# vocal_6btns.net
KiCad netlist of a schematic drawn in EAGLE
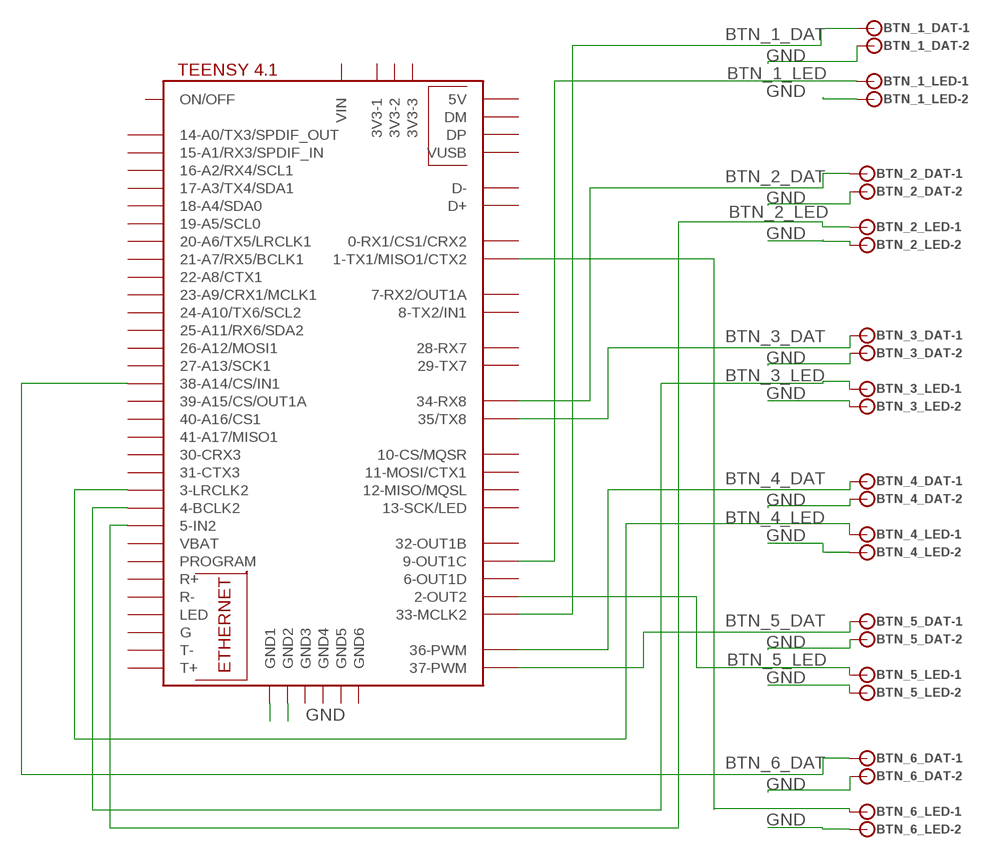
[diagram p0: schematic, sheet 1]

(export (version "E")
  (design (tool "Eeschema 10.0.6"))
  (components
    (comp (ref "BTN_1_DAT")
      (value "JST-XH-2B")
      (footprint "eagle-import:B2B-XH-A")
      (fields (field (name "MF") "JST") (field (name "MPN") "B2B-XH-A"))
      (libsource (lib "eagle-import") (part "JST-XH-2B"))
    )
    (comp (ref "BTN_1_LED")
      (value "JST-XH-2B")
      (footprint "eagle-import:B2B-XH-A")
      (fields (field (name "MF") "JST") (field (name "MPN") "B2B-XH-A"))
      (libsource (lib "eagle-import") (part "JST-XH-2B"))
    )
    (comp (ref "BTN_2_DAT")
      (value "JST-XH-2B")
      (footprint "eagle-import:B2B-XH-A")
      (fields (field (name "MF") "JST") (field (name "MPN") "B2B-XH-A"))
      (libsource (lib "eagle-import") (part "JST-XH-2B"))
    )
    (comp (ref "BTN_2_LED")
      (value "JST-XH-2B")
      (footprint "eagle-import:B2B-XH-A")
      (fields (field (name "MF") "JST") (field (name "MPN") "B2B-XH-A"))
      (libsource (lib "eagle-import") (part "JST-XH-2B"))
    )
    (comp (ref "BTN_3_DAT")
      (value "JST-XH-2B")
      (footprint "eagle-import:B2B-XH-A")
      (fields (field (name "MF") "JST") (field (name "MPN") "B2B-XH-A"))
      (libsource (lib "eagle-import") (part "JST-XH-2B"))
    )
    (comp (ref "BTN_3_LED")
      (value "JST-XH-2B")
      (footprint "eagle-import:B2B-XH-A")
      (fields (field (name "MF") "JST") (field (name "MPN") "B2B-XH-A"))
      (libsource (lib "eagle-import") (part "JST-XH-2B"))
    )
    (comp (ref "BTN_4_DAT")
      (value "JST-XH-2B")
      (footprint "eagle-import:B2B-XH-A")
      (fields (field (name "MF") "JST") (field (name "MPN") "B2B-XH-A"))
      (libsource (lib "eagle-import") (part "JST-XH-2B"))
    )
    (comp (ref "BTN_4_LED")
      (value "JST-XH-2B")
      (footprint "eagle-import:B2B-XH-A")
      (fields (field (name "MF") "JST") (field (name "MPN") "B2B-XH-A"))
      (libsource (lib "eagle-import") (part "JST-XH-2B"))
    )
    (comp (ref "BTN_5_DAT")
      (value "JST-XH-2B")
      (footprint "eagle-import:B2B-XH-A")
      (fields (field (name "MF") "JST") (field (name "MPN") "B2B-XH-A"))
      (libsource (lib "eagle-import") (part "JST-XH-2B"))
    )
    (comp (ref "BTN_5_LED")
      (value "JST-XH-2B")
      (footprint "eagle-import:B2B-XH-A")
      (fields (field (name "MF") "JST") (field (name "MPN") "B2B-XH-A"))
      (libsource (lib "eagle-import") (part "JST-XH-2B"))
    )
    (comp (ref "BTN_6_DAT")
      (value "JST-XH-2B")
      (footprint "eagle-import:B2B-XH-A")
      (fields (field (name "MF") "JST") (field (name "MPN") "B2B-XH-A"))
      (libsource (lib "eagle-import") (part "JST-XH-2B"))
    )
    (comp (ref "BTN_6_LED")
      (value "JST-XH-2B")
      (footprint "eagle-import:B2B-XH-A")
      (fields (field (name "MF") "JST") (field (name "MPN") "B2B-XH-A"))
      (libsource (lib "eagle-import") (part "JST-XH-2B"))
    )
    (comp (ref "U$1")
      (value "TEENSY41")
      (footprint "eagle-import:TEENSY41")
      (libsource (lib "eagle-import") (part "TEENSY41"))
    )
  )
  (nets
    (net (code "1") (name "/BTN_1_DAT") (class "Default")
      (node (ref "BTN_1_DAT") (pin "1") (pinfunction "P_1") (pintype "bidirectional"))
      (node (ref "U$1") (pin "33-MCLK2") (pinfunction "33-MCLK2_33-MCLK2") (pintype "bidirectional"))
    )
    (net (code "2") (name "/BTN_1_LED") (class "Default")
      (node (ref "BTN_1_LED") (pin "1") (pinfunction "P_1") (pintype "bidirectional"))
      (node (ref "U$1") (pin "9-OUT1C") (pinfunction "9-OUT1C_9-OUT1C") (pintype "bidirectional"))
    )
    (net (code "3") (name "/BTN_2_DAT") (class "Default")
      (node (ref "BTN_2_DAT") (pin "1") (pinfunction "P_1") (pintype "bidirectional"))
      (node (ref "U$1") (pin "34-RX8") (pinfunction "34-RX8_34-RX8") (pintype "bidirectional"))
    )
    (net (code "4") (name "/BTN_2_LED") (class "Default")
      (node (ref "BTN_2_LED") (pin "1") (pinfunction "P_1") (pintype "bidirectional"))
      (node (ref "U$1") (pin "5-IN2") (pinfunction "5-IN2_5-IN2") (pintype "bidirectional"))
    )
    (net (code "5") (name "/BTN_3_DAT") (class "Default")
      (node (ref "BTN_3_DAT") (pin "1") (pinfunction "P_1") (pintype "bidirectional"))
      (node (ref "U$1") (pin "35-TX8") (pinfunction "35/TX8_35-TX8") (pintype "bidirectional"))
    )
    (net (code "6") (name "/BTN_3_LED") (class "Default")
      (node (ref "BTN_3_LED") (pin "1") (pinfunction "P_1") (pintype "bidirectional"))
      (node (ref "U$1") (pin "4-BCLK2") (pinfunction "4-BCLK2_4-BCLK2") (pintype "bidirectional"))
    )
    (net (code "7") (name "/BTN_4_DAT") (class "Default")
      (node (ref "BTN_4_DAT") (pin "1") (pinfunction "P_1") (pintype "bidirectional"))
      (node (ref "U$1") (pin "36-PWM") (pinfunction "36-PWM_36-PWM") (pintype "bidirectional"))
    )
    (net (code "8") (name "/BTN_4_LED") (class "Default")
      (node (ref "BTN_4_LED") (pin "1") (pinfunction "P_1") (pintype "bidirectional"))
      (node (ref "U$1") (pin "3-LRCLK2") (pinfunction "3-LRCLK2_3-LRCLK2") (pintype "bidirectional"))
    )
    (net (code "9") (name "/BTN_5_DAT") (class "Default")
      (node (ref "BTN_5_DAT") (pin "1") (pinfunction "P_1") (pintype "bidirectional"))
      (node (ref "U$1") (pin "37-PWM") (pinfunction "37-PWM_37-PWM") (pintype "bidirectional"))
    )
    (net (code "10") (name "/BTN_5_LED") (class "Default")
      (node (ref "BTN_5_LED") (pin "1") (pinfunction "P_1") (pintype "bidirectional"))
      (node (ref "U$1") (pin "2-OUT2") (pinfunction "2-OUT2_2-OUT2") (pintype "bidirectional"))
    )
    (net (code "11") (name "/BTN_6_DAT") (class "Default")
      (node (ref "BTN_6_DAT") (pin "1") (pinfunction "P_1") (pintype "bidirectional"))
      (node (ref "U$1") (pin "38-A14/CS/IN1") (pinfunction "38-A14/CS/IN1_38-A14/CS/IN1") (pintype "bidirectional"))
    )
    (net (code "12") (name "/GND") (class "Default")
      (node (ref "BTN_1_DAT") (pin "2") (pinfunction "P_2") (pintype "bidirectional"))
      (node (ref "BTN_1_LED") (pin "2") (pinfunction "P_2") (pintype "bidirectional"))
      (node (ref "BTN_2_DAT") (pin "2") (pinfunction "P_2") (pintype "bidirectional"))
      (node (ref "BTN_2_LED") (pin "2") (pinfunction "P_2") (pintype "bidirectional"))
      (node (ref "BTN_3_DAT") (pin "2") (pinfunction "P_2") (pintype "bidirectional"))
      (node (ref "BTN_3_LED") (pin "2") (pinfunction "P_2") (pintype "bidirectional"))
      (node (ref "BTN_4_DAT") (pin "2") (pinfunction "P_2") (pintype "bidirectional"))
      (node (ref "BTN_4_LED") (pin "2") (pinfunction "P_2") (pintype "bidirectional"))
      (node (ref "BTN_5_DAT") (pin "2") (pinfunction "P_2") (pintype "bidirectional"))
      (node (ref "BTN_5_LED") (pin "2") (pinfunction "P_2") (pintype "bidirectional"))
      (node (ref "BTN_6_DAT") (pin "2") (pinfunction "P_2") (pintype "bidirectional"))
      (node (ref "BTN_6_LED") (pin "2") (pinfunction "P_2") (pintype "bidirectional"))
      (node (ref "U$1") (pin "GND1") (pinfunction "GND1_GND1") (pintype "bidirectional"))
      (node (ref "U$1") (pin "GND2") (pinfunction "GND2_GND2") (pintype "bidirectional"))
    )
    (net (code "13") (name "Net-(BTN_6_LEDA-P)") (class "Default")
      (node (ref "BTN_6_LED") (pin "1") (pinfunction "P_1") (pintype "bidirectional"))
      (node (ref "U$1") (pin "1-TX1/MISO1/CTX2") (pinfunction "1-TX1/MISO1/CTX2_1-TX1/MISO1/CTX2") (pintype "bidirectional"))
    )
    (net (code "14") (name "unconnected-(U$1-5V-Pad+5V)") (class "Default")
      (node (ref "U$1") (pin "+5V") (pinfunction "5V_+5V") (pintype "bidirectional"))
    )
    (net (code "15") (name "unconnected-(U$1-10-CS{slash}MQSR-Pad10-CS\\MQSR)") (class "Default")
      (node (ref "U$1") (pin "10-CS\\MQSR") (pinfunction "10-CS/MQSR_10-CS\\MQSR") (pintype "bidirectional"))
    )
    (net (code "16") (name "unconnected-(U$1-Pad0-RX1{slash}CS1{slash}CRX2)") (class "Default")
      (node (ref "U$1") (pin "0-RX1/CS1/CRX2") (pinfunction "0-RX1/CS1/CRX2_0-RX1/CS1/CRX2") (pintype "bidirectional"))
    )
    (net (code "17") (name "unconnected-(U$1-Pad3V3-1)") (class "Default")
      (node (ref "U$1") (pin "3V3-1") (pinfunction "3V3-1_3V3-1") (pintype "bidirectional"))
    )
    (net (code "18") (name "unconnected-(U$1-Pad3V3-2)") (class "Default")
      (node (ref "U$1") (pin "3V3-2") (pinfunction "3V3-2_3V3-2") (pintype "bidirectional"))
    )
    (net (code "19") (name "unconnected-(U$1-Pad3V3-3)") (class "Default")
      (node (ref "U$1") (pin "3V3-3") (pinfunction "3V3-3_3V3-3") (pintype "bidirectional"))
    )
    (net (code "20") (name "unconnected-(U$1-Pad6-OUT1D)") (class "Default")
      (node (ref "U$1") (pin "6-OUT1D") (pinfunction "6-OUT1D_6-OUT1D") (pintype "bidirectional"))
    )
    (net (code "21") (name "unconnected-(U$1-Pad7-RX2{slash}OUT1A)") (class "Default")
      (node (ref "U$1") (pin "7-RX2/OUT1A") (pinfunction "7-RX2/OUT1A_7-RX2/OUT1A") (pintype "bidirectional"))
    )
    (net (code "22") (name "unconnected-(U$1-Pad8-TX2{slash}IN1)") (class "Default")
      (node (ref "U$1") (pin "8-TX2/IN1") (pinfunction "8-TX2/IN1_8-TX2/IN1") (pintype "bidirectional"))
    )
    (net (code "23") (name "unconnected-(U$1-Pad11-MOSI{slash}CTX1)") (class "Default")
      (node (ref "U$1") (pin "11-MOSI/CTX1") (pinfunction "11-MOSI/CTX1_11-MOSI/CTX1") (pintype "bidirectional"))
    )
    (net (code "24") (name "unconnected-(U$1-Pad12-MISO{slash}MQSL)") (class "Default")
      (node (ref "U$1") (pin "12-MISO/MQSL") (pinfunction "12-MISO/MQSL_12-MISO/MQSL") (pintype "bidirectional"))
    )
    (net (code "25") (name "unconnected-(U$1-Pad13-SCK{slash}LED)") (class "Default")
      (node (ref "U$1") (pin "13-SCK/LED") (pinfunction "13-SCK/LED_13-SCK/LED") (pintype "bidirectional"))
    )
    (net (code "26") (name "unconnected-(U$1-Pad14-A0{slash}TX3{slash}SPDIF_OUT)") (class "Default")
      (node (ref "U$1") (pin "14-A0/TX3/SPDIF_OUT") (pinfunction "14-A0/TX3/SPDIF_OUT_14-A0/TX3/SPDIF_OUT") (pintype "bidirectional"))
    )
    (net (code "27") (name "unconnected-(U$1-Pad15-A1{slash}RX3{slash}SPDIF_IN)") (class "Default")
      (node (ref "U$1") (pin "15-A1/RX3/SPDIF_IN") (pinfunction "15-A1/RX3/SPDIF_IN_15-A1/RX3/SPDIF_IN") (pintype "bidirectional"))
    )
    (net (code "28") (name "unconnected-(U$1-Pad16-A2{slash}RX4{slash}SCL1)") (class "Default")
      (node (ref "U$1") (pin "16-A2/RX4/SCL1") (pinfunction "16-A2/RX4/SCL1_16-A2/RX4/SCL1") (pintype "bidirectional"))
    )
    (net (code "29") (name "unconnected-(U$1-Pad17-A3{slash}TX4{slash}SDA1)") (class "Default")
      (node (ref "U$1") (pin "17-A3/TX4/SDA1") (pinfunction "17-A3/TX4/SDA1_17-A3/TX4/SDA1") (pintype "bidirectional"))
    )
    (net (code "30") (name "unconnected-(U$1-Pad18-A4{slash}SDA0)") (class "Default")
      (node (ref "U$1") (pin "18-A4/SDA0") (pinfunction "18-A4/SDA0_18-A4/SDA0") (pintype "bidirectional"))
    )
    (net (code "31") (name "unconnected-(U$1-Pad19-A5{slash}SCL0)") (class "Default")
      (node (ref "U$1") (pin "19-A5/SCL0") (pinfunction "19-A5/SCL0_19-A5/SCL0") (pintype "bidirectional"))
    )
    (net (code "32") (name "unconnected-(U$1-Pad20-A6{slash}TX5{slash}LRCLK1)") (class "Default")
      (node (ref "U$1") (pin "20-A6/TX5/LRCLK1") (pinfunction "20-A6/TX5/LRCLK1_20-A6/TX5/LRCLK1") (pintype "bidirectional"))
    )
    (net (code "33") (name "unconnected-(U$1-Pad21-A7{slash}RX5{slash}BCLK1)") (class "Default")
      (node (ref "U$1") (pin "21-A7/RX5/BCLK1") (pinfunction "21-A7/RX5/BCLK1_21-A7/RX5/BCLK1") (pintype "bidirectional"))
    )
    (net (code "34") (name "unconnected-(U$1-Pad22-A8{slash}CTX1)") (class "Default")
      (node (ref "U$1") (pin "22-A8/CTX1") (pinfunction "22-A8/CTX1_22-A8/CTX1") (pintype "bidirectional"))
    )
    (net (code "35") (name "unconnected-(U$1-Pad23-A9{slash}CRX1{slash}MCLK1)") (class "Default")
      (node (ref "U$1") (pin "23-A9/CRX1/MCLK1") (pinfunction "23-A9/CRX1/MCLK1_23-A9/CRX1/MCLK1") (pintype "bidirectional"))
    )
    (net (code "36") (name "unconnected-(U$1-Pad24-A10{slash}TX6{slash}SCL2)") (class "Default")
      (node (ref "U$1") (pin "24-A10/TX6/SCL2") (pinfunction "24-A10/TX6/SCL2_24-A10/TX6/SCL2") (pintype "bidirectional"))
    )
    (net (code "37") (name "unconnected-(U$1-Pad25-A11{slash}RX6{slash}SDA2)") (class "Default")
      (node (ref "U$1") (pin "25-A11/RX6/SDA2") (pinfunction "25-A11/RX6/SDA2_25-A11/RX6/SDA2") (pintype "bidirectional"))
    )
    (net (code "38") (name "unconnected-(U$1-Pad26-A12{slash}MOSI1)") (class "Default")
      (node (ref "U$1") (pin "26-A12/MOSI1") (pinfunction "26-A12/MOSI1_26-A12/MOSI1") (pintype "bidirectional"))
    )
    (net (code "39") (name "unconnected-(U$1-Pad27-A13{slash}SCK1)") (class "Default")
      (node (ref "U$1") (pin "27-A13/SCK1") (pinfunction "27-A13/SCK1_27-A13/SCK1") (pintype "bidirectional"))
    )
    (net (code "40") (name "unconnected-(U$1-Pad28-RX7)") (class "Default")
      (node (ref "U$1") (pin "28-RX7") (pinfunction "28-RX7_28-RX7") (pintype "bidirectional"))
    )
    (net (code "41") (name "unconnected-(U$1-Pad29-TX7)") (class "Default")
      (node (ref "U$1") (pin "29-TX7") (pinfunction "29-TX7_29-TX7") (pintype "bidirectional"))
    )
    (net (code "42") (name "unconnected-(U$1-Pad30-CRX3)") (class "Default")
      (node (ref "U$1") (pin "30-CRX3") (pinfunction "30-CRX3_30-CRX3") (pintype "bidirectional"))
    )
    (net (code "43") (name "unconnected-(U$1-Pad31-CTX3)") (class "Default")
      (node (ref "U$1") (pin "31-CTX3") (pinfunction "31-CTX3_31-CTX3") (pintype "bidirectional"))
    )
    (net (code "44") (name "unconnected-(U$1-Pad32-OUT1B)") (class "Default")
      (node (ref "U$1") (pin "32-OUT1B") (pinfunction "32-OUT1B_32-OUT1B") (pintype "bidirectional"))
    )
    (net (code "45") (name "unconnected-(U$1-Pad39-A15{slash}CS{slash}OUT1A)") (class "Default")
      (node (ref "U$1") (pin "39-A15/CS/OUT1A") (pinfunction "39-A15/CS/OUT1A_39-A15/CS/OUT1A") (pintype "bidirectional"))
    )
    (net (code "46") (name "unconnected-(U$1-Pad40-A16{slash}CS1)") (class "Default")
      (node (ref "U$1") (pin "40-A16/CS1") (pinfunction "40-A16/CS1_40-A16/CS1") (pintype "bidirectional"))
    )
    (net (code "47") (name "unconnected-(U$1-Pad41-A17{slash}MISO1)") (class "Default")
      (node (ref "U$1") (pin "41-A17/MISO1") (pinfunction "41-A17/MISO1_41-A17/MISO1") (pintype "bidirectional"))
    )
    (net (code "48") (name "unconnected-(U$1-PadD+)") (class "Default")
      (node (ref "U$1") (pin "D+") (pinfunction "D+_D+") (pintype "bidirectional"))
    )
    (net (code "49") (name "unconnected-(U$1-PadD-)") (class "Default")
      (node (ref "U$1") (pin "D-") (pinfunction "D-_D-") (pintype "bidirectional"))
    )
    (net (code "50") (name "unconnected-(U$1-PadDM)") (class "Default")
      (node (ref "U$1") (pin "DM") (pinfunction "DM_DM") (pintype "bidirectional"))
    )
    (net (code "51") (name "unconnected-(U$1-PadDP)") (class "Default")
      (node (ref "U$1") (pin "DP") (pinfunction "DP_DP") (pintype "bidirectional"))
    )
    (net (code "52") (name "unconnected-(U$1-PadG)") (class "Default")
      (node (ref "U$1") (pin "G") (pinfunction "G_G") (pintype "bidirectional"))
    )
    (net (code "53") (name "unconnected-(U$1-PadGND3)") (class "Default")
      (node (ref "U$1") (pin "GND3") (pinfunction "GND3_GND3") (pintype "bidirectional"))
    )
    (net (code "54") (name "unconnected-(U$1-PadGND4)") (class "Default")
      (node (ref "U$1") (pin "GND4") (pinfunction "GND4_GND4") (pintype "bidirectional"))
    )
    (net (code "55") (name "unconnected-(U$1-PadGND5)") (class "Default")
      (node (ref "U$1") (pin "GND5") (pinfunction "GND5_GND5") (pintype "bidirectional"))
    )
    (net (code "56") (name "unconnected-(U$1-PadGND6)") (class "Default")
      (node (ref "U$1") (pin "GND6") (pinfunction "GND6_GND6") (pintype "bidirectional"))
    )
    (net (code "57") (name "unconnected-(U$1-PadLED)") (class "Default")
      (node (ref "U$1") (pin "LED") (pinfunction "LED_LED") (pintype "bidirectional"))
    )
    (net (code "58") (name "unconnected-(U$1-PadON{slash}OFF)") (class "Default")
      (node (ref "U$1") (pin "ON/OFF") (pinfunction "ON/OFF_ON/OFF") (pintype "bidirectional"))
    )
    (net (code "59") (name "unconnected-(U$1-PadPROGRAM)") (class "Default")
      (node (ref "U$1") (pin "PROGRAM") (pinfunction "PROGRAM_PROGRAM") (pintype "bidirectional"))
    )
    (net (code "60") (name "unconnected-(U$1-PadR+)") (class "Default")
      (node (ref "U$1") (pin "R+") (pinfunction "R+_R+") (pintype "bidirectional"))
    )
    (net (code "61") (name "unconnected-(U$1-PadR-)") (class "Default")
      (node (ref "U$1") (pin "R-") (pinfunction "R-_R-") (pintype "bidirectional"))
    )
    (net (code "62") (name "unconnected-(U$1-PadT+)") (class "Default")
      (node (ref "U$1") (pin "T+") (pinfunction "T+_T+") (pintype "bidirectional"))
    )
    (net (code "63") (name "unconnected-(U$1-PadT-)") (class "Default")
      (node (ref "U$1") (pin "T-") (pinfunction "T-_T-") (pintype "bidirectional"))
    )
    (net (code "64") (name "unconnected-(U$1-PadVBAT)") (class "Default")
      (node (ref "U$1") (pin "VBAT") (pinfunction "VBAT_VBAT") (pintype "bidirectional"))
    )
    (net (code "65") (name "unconnected-(U$1-PadVIN)") (class "Default")
      (node (ref "U$1") (pin "VIN") (pinfunction "VIN_VIN") (pintype "bidirectional"))
    )
    (net (code "66") (name "unconnected-(U$1-PadVUSB)") (class "Default")
      (node (ref "U$1") (pin "VUSB") (pinfunction "VUSB_VUSB") (pintype "bidirectional"))
    )
  )
)
